# currentSensingBoard.net
KiCad netlist of a schematic drawn in EAGLE
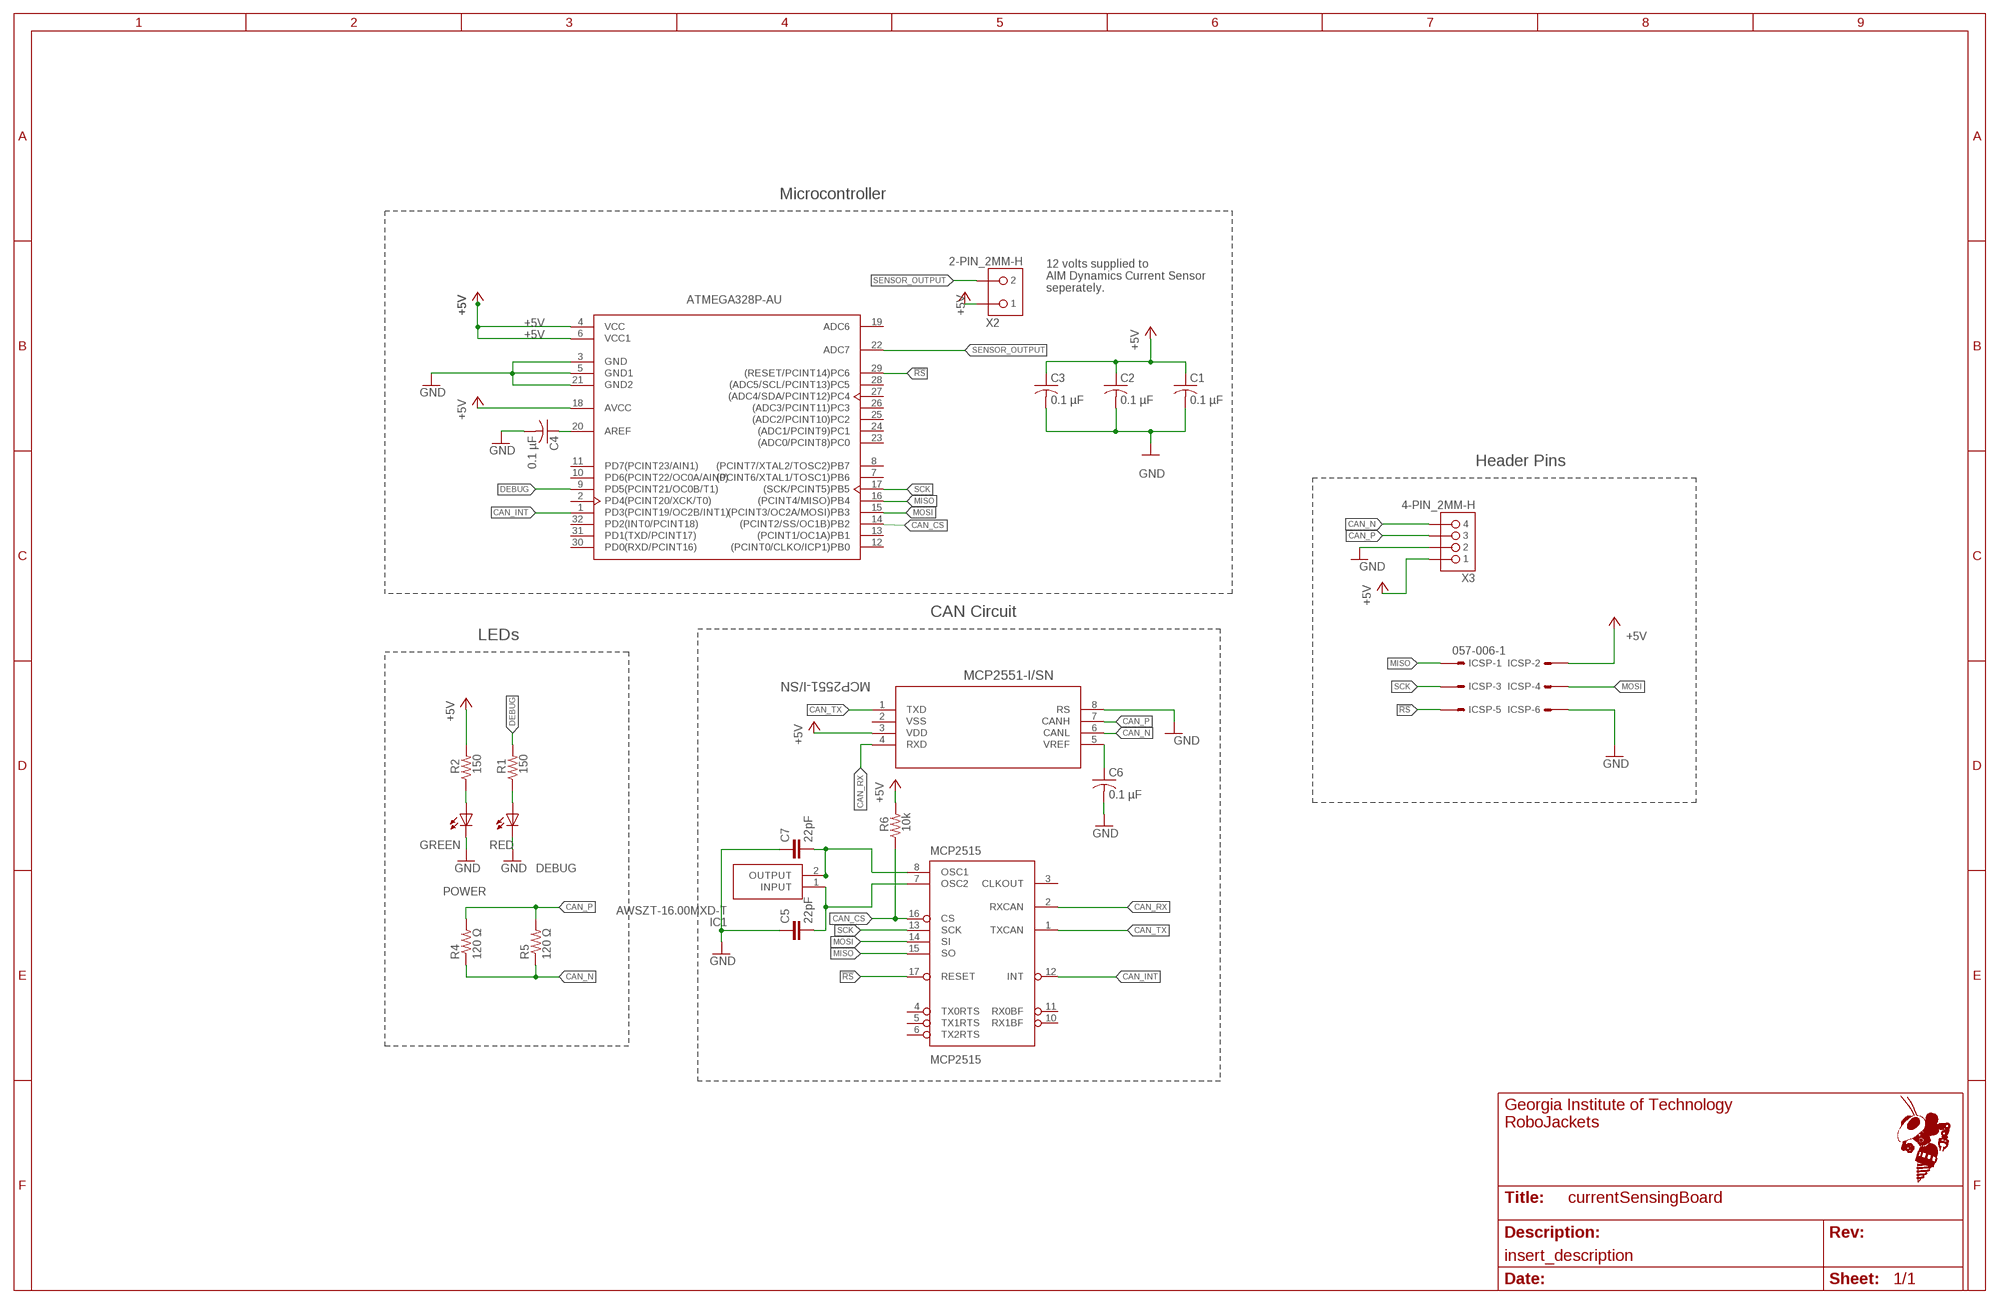
[diagram p0: schematic, sheet 1]

(export (version "E")
  (design (tool "Eeschema 10.0.6"))
  (components
    (comp (ref "ATMEGA328P-AU(V1)")
      (value "ATMEGA328P-AU (V1)")
      (footprint "eagle-import:TQFP-32")
      (fields
        (field (name "DIGIKEY_PART_NUMBER") "ATMEGA328P-AU-ND")
        (field (name "MANUFACTURER") "Microchip Technology")
        (field (name "MPN") "ATMEGA328P-AU")
        (field (name "PARTS_NAME") "ATMEGA328P-AU")
        (field (name "CREATED_BY") "PCBLayout.com")
      )
      (libsource (lib "eagle-import") (part "ATMEGA328P-AU"))
    )
    (comp (ref "C1")
      (value "0.1 µF")
      (footprint "eagle-import:C0603")
      (libsource (lib "eagle-import") (part "C-USC0603"))
    )
    (comp (ref "C2")
      (value "0.1 µF")
      (footprint "eagle-import:C0603")
      (libsource (lib "eagle-import") (part "C-USC0603"))
    )
    (comp (ref "C3")
      (value "0.1 µF")
      (footprint "eagle-import:C0603")
      (libsource (lib "eagle-import") (part "C-USC0603"))
    )
    (comp (ref "C4")
      (value "0.1 µF")
      (footprint "eagle-import:C0603")
      (libsource (lib "eagle-import") (part "C-USC0603"))
    )
    (comp (ref "C5")
      (value "22pF")
      (footprint "eagle-import:0603-CAP")
      (libsource (lib "eagle-import") (part "22PF-50V-5%(0603)"))
    )
    (comp (ref "C6")
      (value "0.1 µF")
      (footprint "eagle-import:C0603")
      (libsource (lib "eagle-import") (part "C-USC0603"))
    )
    (comp (ref "C7")
      (value "22pF")
      (footprint "eagle-import:0603-CAP")
      (libsource (lib "eagle-import") (part "22PF-50V-5%(0603)"))
    )
    (comp (ref "DEBUG")
      (value "RED")
      (footprint "eagle-import:CHIP-LED0603")
      (fields (field (name "MPN") "LTST-C191KRKT"))
      (libsource (lib "eagle-import") (part "LED-SMD-RED"))
    )
    (comp (ref "IC1")
      (value "AWSZT-16.00MXD-T")
      (footprint "eagle-import:AWSZT1600MXDT")
      (fields (field (name "MOUSER_PART_NUMBER") "815-AWSZT-16.00MXDT"))
      (libsource (lib "eagle-import") (part "AWSZT-16.00MXD-T"))
    )
    (comp (ref "ICSP")
      (value "057-006-1")
      (footprint "eagle-import:057-006-1")
      (libsource (lib "eagle-import") (part "057-006-1"))
    )
    (comp (ref "MCP2515")
      (value "MCP2515")
      (footprint "eagle-import:SO-18W")
      (libsource (lib "eagle-import") (part "MCP2510SO"))
    )
    (comp (ref "MCP2551-I/SN")
      (value "MCP2551-I/SN")
      (footprint "eagle-import:SOIC8-N_MC")
      (fields (field (name "MANUFACTURER_PART_NUMBER") "MCP2551ISN"))
      (libsource (lib "eagle-import") (part "MCP2551-I/SN"))
    )
    (comp (ref "POWER")
      (value "GREEN")
      (footprint "eagle-import:CHIP-LED0603")
      (fields (field (name "MPN") "LTST-C191KGKT"))
      (libsource (lib "eagle-import") (part "LED-SMD-GREEN"))
    )
    (comp (ref "R1")
      (value "150")
      (footprint "eagle-import:R0603")
      (libsource (lib "eagle-import") (part "R-US_R0603"))
    )
    (comp (ref "R2")
      (value "150")
      (footprint "eagle-import:R0603")
      (libsource (lib "eagle-import") (part "R-US_R0603"))
    )
    (comp (ref "R4")
      (value "120 Ω")
      (footprint "eagle-import:R0603")
      (libsource (lib "eagle-import") (part "R-US_R0603"))
    )
    (comp (ref "R5")
      (value "120 Ω")
      (footprint "eagle-import:R0603")
      (libsource (lib "eagle-import") (part "R-US_R0603"))
    )
    (comp (ref "R6")
      (value "10k")
      (footprint "eagle-import:R0603")
      (libsource (lib "eagle-import") (part "R-US_R0603"))
    )
    (comp (ref "X2")
      (value "2-PIN_2MM-H")
      (footprint "eagle-import:2MM-2-H")
      (libsource (lib "eagle-import") (part "2-PIN_2MM-H"))
    )
    (comp (ref "X3")
      (value "4-PIN_2MM-H")
      (footprint "eagle-import:2MM-4-H")
      (fields (field (name "MPN") "0353630460"))
      (libsource (lib "eagle-import") (part "4-PIN_2MM-H"))
    )
  )
  (nets
    (net (code "1") (name "+5V") (class "Default")
      (node (ref "ATMEGA328P-AU(V1)") (pin "18") (pinfunction "AVCC_18") (pintype "power_in"))
      (node (ref "ATMEGA328P-AU(V1)") (pin "4") (pinfunction "VCC_4") (pintype "power_in"))
      (node (ref "ATMEGA328P-AU(V1)") (pin "6") (pinfunction "VCC1_6") (pintype "power_in"))
      (node (ref "C1") (pin "1") (pinfunction "1_1") (pintype "passive"))
      (node (ref "C2") (pin "1") (pinfunction "1_1") (pintype "passive"))
      (node (ref "C3") (pin "1") (pinfunction "1_1") (pintype "passive"))
      (node (ref "ICSP") (pin "2") (pinfunction "S_2") (pintype "passive"))
      (node (ref "MCP2551-I/SN") (pin "3") (pinfunction "VDD_3") (pintype "passive"))
      (node (ref "R2") (pin "2") (pinfunction "2_2") (pintype "passive"))
      (node (ref "R6") (pin "2") (pinfunction "2_2") (pintype "passive"))
      (node (ref "X2") (pin "1") (pinfunction "1_1") (pintype "bidirectional"))
      (node (ref "X3") (pin "1") (pinfunction "1_1") (pintype "passive"))
    )
    (net (code "2") (name "/~{RS}") (class "Default")
      (node (ref "ATMEGA328P-AU(V1)") (pin "29") (pinfunction "(RESET/PCINT14)PC6_29") (pintype "bidirectional"))
      (node (ref "ICSP") (pin "5") (pinfunction "S_5") (pintype "passive"))
      (node (ref "MCP2515") (pin "17") (pinfunction "RESET_17") (pintype "input"))
    )
    (net (code "3") (name "CAN_CS") (class "Default")
      (node (ref "ATMEGA328P-AU(V1)") (pin "14") (pinfunction "(PCINT2/SS/OC1B)PB2_14") (pintype "bidirectional"))
      (node (ref "MCP2515") (pin "16") (pinfunction "CS_16") (pintype "input"))
      (node (ref "R6") (pin "1") (pinfunction "1_1") (pintype "passive"))
    )
    (net (code "4") (name "CAN_INT") (class "Default")
      (node (ref "ATMEGA328P-AU(V1)") (pin "1") (pinfunction "PD3(PCINT19/OC2B/INT1)_1") (pintype "bidirectional"))
      (node (ref "MCP2515") (pin "12") (pinfunction "INT_12") (pintype "output"))
    )
    (net (code "5") (name "CAN_N") (class "Default")
      (node (ref "MCP2551-I/SN") (pin "6") (pinfunction "CANL_6") (pintype "passive"))
      (node (ref "R4") (pin "1") (pinfunction "1_1") (pintype "passive"))
      (node (ref "R5") (pin "1") (pinfunction "1_1") (pintype "passive"))
      (node (ref "X3") (pin "4") (pinfunction "4_4") (pintype "passive"))
    )
    (net (code "6") (name "CAN_P") (class "Default")
      (node (ref "MCP2551-I/SN") (pin "7") (pinfunction "CANH_7") (pintype "passive"))
      (node (ref "R4") (pin "2") (pinfunction "2_2") (pintype "passive"))
      (node (ref "R5") (pin "2") (pinfunction "2_2") (pintype "passive"))
      (node (ref "X3") (pin "3") (pinfunction "3_3") (pintype "passive"))
    )
    (net (code "7") (name "CAN_RX") (class "Default")
      (node (ref "MCP2515") (pin "2") (pinfunction "RXCAN_2") (pintype "input"))
      (node (ref "MCP2551-I/SN") (pin "4") (pinfunction "RXD_4") (pintype "passive"))
    )
    (net (code "8") (name "CAN_TX") (class "Default")
      (node (ref "MCP2515") (pin "1") (pinfunction "TXCAN_1") (pintype "output"))
      (node (ref "MCP2551-I/SN") (pin "1") (pinfunction "TXD_1") (pintype "passive"))
    )
    (net (code "9") (name "DEBUG") (class "Default")
      (node (ref "ATMEGA328P-AU(V1)") (pin "9") (pinfunction "PD5(PCINT21/OC0B/T1)_9") (pintype "bidirectional"))
      (node (ref "R1") (pin "2") (pinfunction "2_2") (pintype "passive"))
    )
    (net (code "10") (name "GND") (class "Default")
      (node (ref "ATMEGA328P-AU(V1)") (pin "21") (pinfunction "GND2_21") (pintype "power_in"))
      (node (ref "ATMEGA328P-AU(V1)") (pin "3") (pinfunction "GND_3") (pintype "power_in"))
      (node (ref "ATMEGA328P-AU(V1)") (pin "5") (pinfunction "GND1_5") (pintype "power_in"))
      (node (ref "C1") (pin "2") (pinfunction "2_2") (pintype "passive"))
      (node (ref "C2") (pin "2") (pinfunction "2_2") (pintype "passive"))
      (node (ref "C3") (pin "2") (pinfunction "2_2") (pintype "passive"))
      (node (ref "C4") (pin "2") (pinfunction "2_2") (pintype "passive"))
      (node (ref "C5") (pin "1") (pinfunction "1_1") (pintype "passive"))
      (node (ref "C6") (pin "2") (pinfunction "2_2") (pintype "passive"))
      (node (ref "C7") (pin "1") (pinfunction "1_1") (pintype "passive"))
      (node (ref "DEBUG") (pin "C") (pinfunction "K_C") (pintype "passive"))
      (node (ref "ICSP") (pin "6") (pinfunction "S_6") (pintype "passive"))
      (node (ref "MCP2551-I/SN") (pin "8") (pinfunction "RS_8") (pintype "passive"))
      (node (ref "POWER") (pin "C") (pinfunction "K_C") (pintype "passive"))
      (node (ref "X3") (pin "2") (pinfunction "2_2") (pintype "passive"))
    )
    (net (code "11") (name "MISO") (class "Default")
      (node (ref "ATMEGA328P-AU(V1)") (pin "16") (pinfunction "(PCINT4/MISO)PB4_16") (pintype "bidirectional"))
      (node (ref "ICSP") (pin "1") (pinfunction "S_1") (pintype "passive"))
      (node (ref "MCP2515") (pin "15") (pinfunction "SO_15") (pintype "output"))
    )
    (net (code "12") (name "MOSI") (class "Default")
      (node (ref "ATMEGA328P-AU(V1)") (pin "15") (pinfunction "(PCINT3/OC2A/MOSI)PB3_15") (pintype "bidirectional"))
      (node (ref "ICSP") (pin "4") (pinfunction "S_4") (pintype "passive"))
      (node (ref "MCP2515") (pin "14") (pinfunction "SI_14") (pintype "input"))
    )
    (net (code "13") (name "Net-(ATMEGA328P-AU(V1)-AREF)") (class "Default")
      (node (ref "ATMEGA328P-AU(V1)") (pin "20") (pinfunction "AREF_20") (pintype "power_in"))
      (node (ref "C4") (pin "1") (pinfunction "1_1") (pintype "passive"))
    )
    (net (code "14") (name "Net-(DEBUG-PadA)") (class "Default")
      (node (ref "DEBUG") (pin "A") (pinfunction "A_A") (pintype "passive"))
      (node (ref "R1") (pin "1") (pinfunction "1_1") (pintype "passive"))
    )
    (net (code "15") (name "Net-(IC1-INPUT)") (class "Default")
      (node (ref "C5") (pin "2") (pinfunction "2_2") (pintype "passive"))
      (node (ref "IC1") (pin "1") (pinfunction "INPUT_1") (pintype "bidirectional"))
      (node (ref "MCP2515") (pin "7") (pinfunction "OSC2_7") (pintype "output"))
    )
    (net (code "16") (name "Net-(IC1-OUTPUT)") (class "Default")
      (node (ref "C7") (pin "2") (pinfunction "2_2") (pintype "passive"))
      (node (ref "IC1") (pin "2") (pinfunction "OUTPUT_2") (pintype "bidirectional"))
      (node (ref "MCP2515") (pin "8") (pinfunction "OSC1_8") (pintype "input"))
    )
    (net (code "17") (name "Net-(MCP2551-I/SN-VREF)") (class "Default")
      (node (ref "C6") (pin "1") (pinfunction "1_1") (pintype "passive"))
      (node (ref "MCP2551-I/SN") (pin "5") (pinfunction "VREF_5") (pintype "passive"))
    )
    (net (code "18") (name "Net-(POWER-PadA)") (class "Default")
      (node (ref "POWER") (pin "A") (pinfunction "A_A") (pintype "passive"))
      (node (ref "R2") (pin "1") (pinfunction "1_1") (pintype "passive"))
    )
    (net (code "19") (name "SCK") (class "Default")
      (node (ref "ATMEGA328P-AU(V1)") (pin "17") (pinfunction "(SCK/PCINT5)PB5_17") (pintype "bidirectional"))
      (node (ref "ICSP") (pin "3") (pinfunction "S_3") (pintype "passive"))
      (node (ref "MCP2515") (pin "13") (pinfunction "SCK_13") (pintype "input"))
    )
    (net (code "20") (name "SENSOR_OUTPUT") (class "Default")
      (node (ref "ATMEGA328P-AU(V1)") (pin "22") (pinfunction "ADC7_22") (pintype "input"))
      (node (ref "X2") (pin "2") (pinfunction "2_2") (pintype "bidirectional"))
    )
    (net (code "21") (name "unconnected-(ATMEGA328P-AU(V1)-(ADC0{slash}PCINT8)PC0-Pad23)") (class "Default")
      (node (ref "ATMEGA328P-AU(V1)") (pin "23") (pinfunction "(ADC0/PCINT8)PC0_23") (pintype "bidirectional"))
    )
    (net (code "22") (name "unconnected-(ATMEGA328P-AU(V1)-(ADC1{slash}PCINT9)PC1-Pad24)") (class "Default")
      (node (ref "ATMEGA328P-AU(V1)") (pin "24") (pinfunction "(ADC1/PCINT9)PC1_24") (pintype "bidirectional"))
    )
    (net (code "23") (name "unconnected-(ATMEGA328P-AU(V1)-(ADC2{slash}PCINT10)PC2-Pad25)") (class "Default")
      (node (ref "ATMEGA328P-AU(V1)") (pin "25") (pinfunction "(ADC2/PCINT10)PC2_25") (pintype "bidirectional"))
    )
    (net (code "24") (name "unconnected-(ATMEGA328P-AU(V1)-(ADC3{slash}PCINT11)PC3-Pad26)") (class "Default")
      (node (ref "ATMEGA328P-AU(V1)") (pin "26") (pinfunction "(ADC3/PCINT11)PC3_26") (pintype "bidirectional"))
    )
    (net (code "25") (name "unconnected-(ATMEGA328P-AU(V1)-(ADC4{slash}SDA{slash}PCINT12)PC4-Pad27)") (class "Default")
      (node (ref "ATMEGA328P-AU(V1)") (pin "27") (pinfunction "(ADC4/SDA/PCINT12)PC4_27") (pintype "bidirectional"))
    )
    (net (code "26") (name "unconnected-(ATMEGA328P-AU(V1)-(ADC5{slash}SCL{slash}PCINT13)PC5-Pad28)") (class "Default")
      (node (ref "ATMEGA328P-AU(V1)") (pin "28") (pinfunction "(ADC5/SCL/PCINT13)PC5_28") (pintype "bidirectional"))
    )
    (net (code "27") (name "unconnected-(ATMEGA328P-AU(V1)-(PCINT0{slash}CLKO{slash}ICP1)PB0-Pad12)") (class "Default")
      (node (ref "ATMEGA328P-AU(V1)") (pin "12") (pinfunction "(PCINT0/CLKO/ICP1)PB0_12") (pintype "bidirectional"))
    )
    (net (code "28") (name "unconnected-(ATMEGA328P-AU(V1)-(PCINT1{slash}OC1A)PB1-Pad13)") (class "Default")
      (node (ref "ATMEGA328P-AU(V1)") (pin "13") (pinfunction "(PCINT1/OC1A)PB1_13") (pintype "bidirectional"))
    )
    (net (code "29") (name "unconnected-(ATMEGA328P-AU(V1)-(PCINT6{slash}XTAL1{slash}TOSC1)PB6-Pad7)") (class "Default")
      (node (ref "ATMEGA328P-AU(V1)") (pin "7") (pinfunction "(PCINT6/XTAL1/TOSC1)PB6_7") (pintype "bidirectional"))
    )
    (net (code "30") (name "unconnected-(ATMEGA328P-AU(V1)-(PCINT7{slash}XTAL2{slash}TOSC2)PB7-Pad8)") (class "Default")
      (node (ref "ATMEGA328P-AU(V1)") (pin "8") (pinfunction "(PCINT7/XTAL2/TOSC2)PB7_8") (pintype "bidirectional"))
    )
    (net (code "31") (name "unconnected-(ATMEGA328P-AU(V1)-ADC6-Pad19)") (class "Default")
      (node (ref "ATMEGA328P-AU(V1)") (pin "19") (pinfunction "ADC6_19") (pintype "input"))
    )
    (net (code "32") (name "unconnected-(ATMEGA328P-AU(V1)-PD0(RXD{slash}PCINT16)-Pad30)") (class "Default")
      (node (ref "ATMEGA328P-AU(V1)") (pin "30") (pinfunction "PD0(RXD/PCINT16)_30") (pintype "bidirectional"))
    )
    (net (code "33") (name "unconnected-(ATMEGA328P-AU(V1)-PD1(TXD{slash}PCINT17)-Pad31)") (class "Default")
      (node (ref "ATMEGA328P-AU(V1)") (pin "31") (pinfunction "PD1(TXD/PCINT17)_31") (pintype "bidirectional"))
    )
    (net (code "34") (name "unconnected-(ATMEGA328P-AU(V1)-PD2(INT0{slash}PCINT18)-Pad32)") (class "Default")
      (node (ref "ATMEGA328P-AU(V1)") (pin "32") (pinfunction "PD2(INT0/PCINT18)_32") (pintype "bidirectional"))
    )
    (net (code "35") (name "unconnected-(ATMEGA328P-AU(V1)-PD4(PCINT20{slash}XCK{slash}T0)-Pad2)") (class "Default")
      (node (ref "ATMEGA328P-AU(V1)") (pin "2") (pinfunction "PD4(PCINT20/XCK/T0)_2") (pintype "bidirectional"))
    )
    (net (code "36") (name "unconnected-(ATMEGA328P-AU(V1)-PD6(PCINT22{slash}OC0A{slash}AIN0)-Pad10)") (class "Default")
      (node (ref "ATMEGA328P-AU(V1)") (pin "10") (pinfunction "PD6(PCINT22/OC0A/AIN0)_10") (pintype "bidirectional"))
    )
    (net (code "37") (name "unconnected-(ATMEGA328P-AU(V1)-PD7(PCINT23{slash}AIN1)-Pad11)") (class "Default")
      (node (ref "ATMEGA328P-AU(V1)") (pin "11") (pinfunction "PD7(PCINT23/AIN1)_11") (pintype "bidirectional"))
    )
    (net (code "38") (name "unconnected-(MCP2515A-CLKOUT-Pad3)") (class "Default")
      (node (ref "MCP2515") (pin "3") (pinfunction "CLKOUT_3") (pintype "output"))
    )
    (net (code "39") (name "unconnected-(MCP2515A-RX0BF-Pad11)") (class "Default")
      (node (ref "MCP2515") (pin "11") (pinfunction "RX0BF_11") (pintype "output"))
    )
    (net (code "40") (name "unconnected-(MCP2515A-RX1BF-Pad10)") (class "Default")
      (node (ref "MCP2515") (pin "10") (pinfunction "RX1BF_10") (pintype "output"))
    )
    (net (code "41") (name "unconnected-(MCP2515A-TX0RTS-Pad4)") (class "Default")
      (node (ref "MCP2515") (pin "4") (pinfunction "TX0RTS_4") (pintype "input"))
    )
    (net (code "42") (name "unconnected-(MCP2515A-TX1RTS-Pad5)") (class "Default")
      (node (ref "MCP2515") (pin "5") (pinfunction "TX1RTS_5") (pintype "input"))
    )
    (net (code "43") (name "unconnected-(MCP2515A-TX2RTS-Pad6)") (class "Default")
      (node (ref "MCP2515") (pin "6") (pinfunction "TX2RTS_6") (pintype "input"))
    )
    (net (code "44") (name "unconnected-(MCP2551-I/SN-VSS-Pad2)") (class "Default")
      (node (ref "MCP2551-I/SN") (pin "2") (pinfunction "VSS_2") (pintype "passive"))
    )
  )
)
